# 5_-Display.net
KiCad netlist of a schematic drawn in Altium Designer
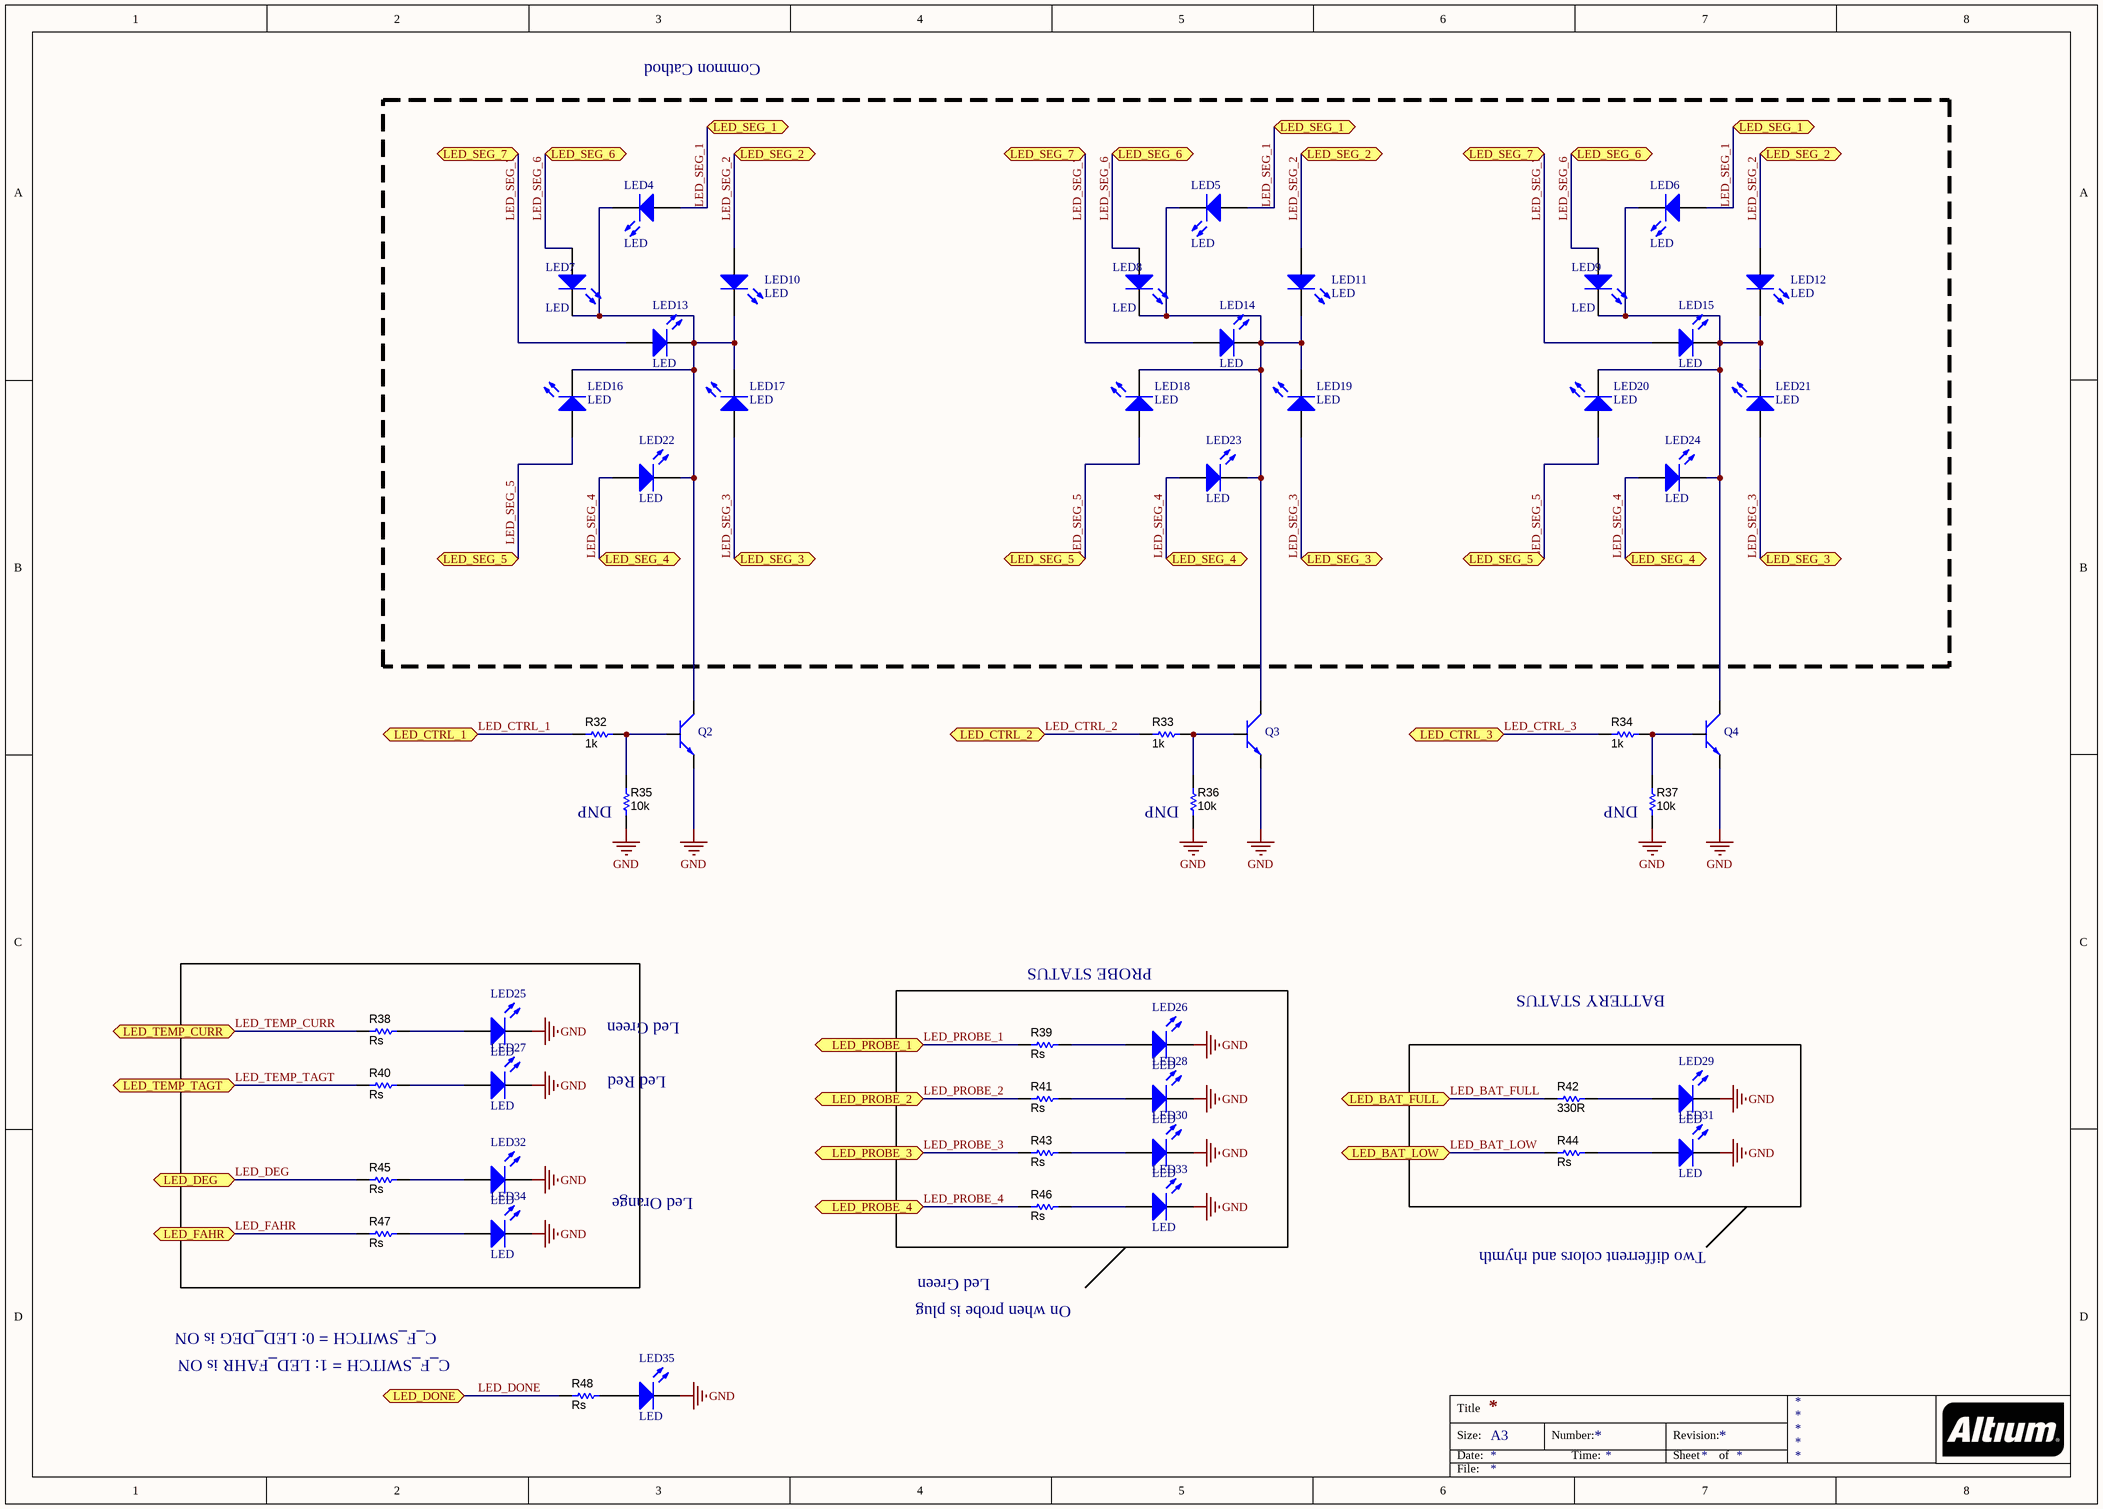
[diagram p0: [5]-Display.SchDoc]

(export (version "E")
  (design (tool "Eeschema 10.0.6"))
  (components
    (comp (ref "LED4")
      (value "LED")
      (footprint "LED-0603-YELLOW")
      (description "Typical INFRARED GaAs LED")
      (fields (field (name "PUBLISHER") "Altium Limited"))
      (libsource (lib "VTEKLib") (part "LED"))
    )
    (comp (ref "LED5")
      (value "LED")
      (footprint "LED-0603-YELLOW")
      (description "Typical INFRARED GaAs LED")
      (fields (field (name "PUBLISHER") "Altium Limited"))
      (libsource (lib "VTEKLib") (part "LED"))
    )
    (comp (ref "LED6")
      (value "LED")
      (footprint "LED-0603-YELLOW")
      (description "Typical INFRARED GaAs LED")
      (fields (field (name "PUBLISHER") "Altium Limited"))
      (libsource (lib "VTEKLib") (part "LED"))
    )
    (comp (ref "LED7")
      (value "LED")
      (footprint "LED-0603-YELLOW")
      (description "Typical INFRARED GaAs LED")
      (fields (field (name "PUBLISHER") "Altium Limited"))
      (libsource (lib "VTEKLib") (part "LED"))
    )
    (comp (ref "LED8")
      (value "LED")
      (footprint "LED-0603-YELLOW")
      (description "Typical INFRARED GaAs LED")
      (fields (field (name "PUBLISHER") "Altium Limited"))
      (libsource (lib "VTEKLib") (part "LED"))
    )
    (comp (ref "LED9")
      (value "LED")
      (footprint "LED-0603-YELLOW")
      (description "Typical INFRARED GaAs LED")
      (fields (field (name "PUBLISHER") "Altium Limited"))
      (libsource (lib "VTEKLib") (part "LED"))
    )
    (comp (ref "LED10")
      (value "LED")
      (footprint "LED-0603-YELLOW")
      (description "Typical INFRARED GaAs LED")
      (fields (field (name "PUBLISHER") "Altium Limited"))
      (libsource (lib "VTEKLib") (part "LED"))
    )
    (comp (ref "LED11")
      (value "LED")
      (footprint "LED-0603-YELLOW")
      (description "Typical INFRARED GaAs LED")
      (fields (field (name "PUBLISHER") "Altium Limited"))
      (libsource (lib "VTEKLib") (part "LED"))
    )
    (comp (ref "LED12")
      (value "LED")
      (footprint "LED-0603-YELLOW")
      (description "Typical INFRARED GaAs LED")
      (fields (field (name "PUBLISHER") "Altium Limited"))
      (libsource (lib "VTEKLib") (part "LED"))
    )
    (comp (ref "LED13")
      (value "LED")
      (footprint "LED-0603-YELLOW")
      (description "Typical INFRARED GaAs LED")
      (fields (field (name "PUBLISHER") "Altium Limited"))
      (libsource (lib "VTEKLib") (part "LED"))
    )
    (comp (ref "LED14")
      (value "LED")
      (footprint "LED-0603-YELLOW")
      (description "Typical INFRARED GaAs LED")
      (fields (field (name "PUBLISHER") "Altium Limited"))
      (libsource (lib "VTEKLib") (part "LED"))
    )
    (comp (ref "LED15")
      (value "LED")
      (footprint "LED-0603-YELLOW")
      (description "Typical INFRARED GaAs LED")
      (fields (field (name "PUBLISHER") "Altium Limited"))
      (libsource (lib "VTEKLib") (part "LED"))
    )
    (comp (ref "LED16")
      (value "LED")
      (footprint "LED-0603-YELLOW")
      (description "Typical INFRARED GaAs LED")
      (fields (field (name "PUBLISHER") "Altium Limited"))
      (libsource (lib "VTEKLib") (part "LED"))
    )
    (comp (ref "LED17")
      (value "LED")
      (footprint "LED-0603-YELLOW")
      (description "Typical INFRARED GaAs LED")
      (fields (field (name "PUBLISHER") "Altium Limited"))
      (libsource (lib "VTEKLib") (part "LED"))
    )
    (comp (ref "LED18")
      (value "LED")
      (footprint "LED-0603-YELLOW")
      (description "Typical INFRARED GaAs LED")
      (fields (field (name "PUBLISHER") "Altium Limited"))
      (libsource (lib "VTEKLib") (part "LED"))
    )
    (comp (ref "LED19")
      (value "LED")
      (footprint "LED-0603-YELLOW")
      (description "Typical INFRARED GaAs LED")
      (fields (field (name "PUBLISHER") "Altium Limited"))
      (libsource (lib "VTEKLib") (part "LED"))
    )
    (comp (ref "LED20")
      (value "LED")
      (footprint "LED-0603-YELLOW")
      (description "Typical INFRARED GaAs LED")
      (fields (field (name "PUBLISHER") "Altium Limited"))
      (libsource (lib "VTEKLib") (part "LED"))
    )
    (comp (ref "LED21")
      (value "LED")
      (footprint "LED-0603-YELLOW")
      (description "Typical INFRARED GaAs LED")
      (fields (field (name "PUBLISHER") "Altium Limited"))
      (libsource (lib "VTEKLib") (part "LED"))
    )
    (comp (ref "LED22")
      (value "LED")
      (footprint "LED-0603-YELLOW")
      (description "Typical INFRARED GaAs LED")
      (fields (field (name "PUBLISHER") "Altium Limited"))
      (libsource (lib "VTEKLib") (part "LED"))
    )
    (comp (ref "LED23")
      (value "LED")
      (footprint "LED-0603-YELLOW")
      (description "Typical INFRARED GaAs LED")
      (fields (field (name "PUBLISHER") "Altium Limited"))
      (libsource (lib "VTEKLib") (part "LED"))
    )
    (comp (ref "LED24")
      (value "LED")
      (footprint "LED-0603-YELLOW")
      (description "Typical INFRARED GaAs LED")
      (fields (field (name "PUBLISHER") "Altium Limited"))
      (libsource (lib "VTEKLib") (part "LED"))
    )
    (comp (ref "LED25")
      (value "LED")
      (footprint "LED-0603-YELLOW")
      (description "Typical INFRARED GaAs LED")
      (fields (field (name "PUBLISHER") "Altium Limited"))
      (libsource (lib "VTEKLib") (part "LED"))
    )
    (comp (ref "LED26")
      (value "LED")
      (footprint "LED-0603-YELLOW")
      (description "Typical INFRARED GaAs LED")
      (fields (field (name "PUBLISHER") "Altium Limited"))
      (libsource (lib "VTEKLib") (part "LED"))
    )
    (comp (ref "LED27")
      (value "LED")
      (footprint "LED-0603-YELLOW")
      (description "Typical INFRARED GaAs LED")
      (fields (field (name "PUBLISHER") "Altium Limited"))
      (libsource (lib "VTEKLib") (part "LED"))
    )
    (comp (ref "LED28")
      (value "LED")
      (footprint "LED-0603-YELLOW")
      (description "Typical INFRARED GaAs LED")
      (fields (field (name "PUBLISHER") "Altium Limited"))
      (libsource (lib "VTEKLib") (part "LED"))
    )
    (comp (ref "LED29")
      (value "LED")
      (footprint "LED-0603-YELLOW")
      (description "Typical INFRARED GaAs LED")
      (fields (field (name "PUBLISHER") "Altium Limited"))
      (libsource (lib "VTEKLib") (part "LED"))
    )
    (comp (ref "LED30")
      (value "LED")
      (footprint "LED-0603-YELLOW")
      (description "Typical INFRARED GaAs LED")
      (fields (field (name "PUBLISHER") "Altium Limited"))
      (libsource (lib "VTEKLib") (part "LED"))
    )
    (comp (ref "LED31")
      (value "LED")
      (footprint "LED-0603-YELLOW")
      (description "Typical INFRARED GaAs LED")
      (fields (field (name "PUBLISHER") "Altium Limited"))
      (libsource (lib "VTEKLib") (part "LED"))
    )
    (comp (ref "LED32")
      (value "LED")
      (footprint "LED-0603-YELLOW")
      (description "Typical INFRARED GaAs LED")
      (fields (field (name "PUBLISHER") "Altium Limited"))
      (libsource (lib "VTEKLib") (part "LED"))
    )
    (comp (ref "LED33")
      (value "LED")
      (footprint "LED-0603-YELLOW")
      (description "Typical INFRARED GaAs LED")
      (fields (field (name "PUBLISHER") "Altium Limited"))
      (libsource (lib "VTEKLib") (part "LED"))
    )
    (comp (ref "LED34")
      (value "LED")
      (footprint "LED-0603-YELLOW")
      (description "Typical INFRARED GaAs LED")
      (fields (field (name "PUBLISHER") "Altium Limited"))
      (libsource (lib "VTEKLib") (part "LED"))
    )
    (comp (ref "LED35")
      (value "LED")
      (footprint "LED-0603-YELLOW")
      (description "Typical INFRARED GaAs LED")
      (fields (field (name "PUBLISHER") "Altium Limited"))
      (libsource (lib "VTEKLib") (part "LED"))
    )
    (comp (ref "Q2")
      (value "MMBT2222A")
      (footprint "SOT23A")
      (description "NPN switching transistor  40V 600mA SOT23")
      (fields (field (name "MANUFACTURER") "Fairchild"))
      (libsource (lib "Cty1") (part "MMBT2222A"))
    )
    (comp (ref "Q3")
      (value "MMBT2222A")
      (footprint "SOT23A")
      (description "NPN switching transistor  40V 600mA SOT23")
      (fields (field (name "MANUFACTURER") "Fairchild"))
      (libsource (lib "Cty1") (part "MMBT2222A"))
    )
    (comp (ref "Q4")
      (value "MMBT2222A")
      (footprint "SOT23A")
      (description "NPN switching transistor  40V 600mA SOT23")
      (fields (field (name "MANUFACTURER") "Fairchild"))
      (libsource (lib "Cty1") (part "MMBT2222A"))
    )
    (comp (ref "R32")
      (value "1k")
      (footprint "0603")
      (description "RES, 1.00k ohm, 1%, 0.1W, 0603")
      (fields
        (field (name "PARTNUMBER") "CRCW06031K00FKEA")
        (field (name "MANUFACTURER") "Vishay-Dale")
        (field (name "PUBLISHER") "Texas Instruments")
      )
      (libsource (lib "tuongpv2") (part "R0603"))
    )
    (comp (ref "R33")
      (value "1k")
      (footprint "0603")
      (description "RES, 1.00k ohm, 1%, 0.1W, 0603")
      (fields
        (field (name "PARTNUMBER") "CRCW06031K00FKEA")
        (field (name "MANUFACTURER") "Vishay-Dale")
        (field (name "PUBLISHER") "Texas Instruments")
      )
      (libsource (lib "tuongpv2") (part "R0603"))
    )
    (comp (ref "R34")
      (value "1k")
      (footprint "0603")
      (description "RES, 1.00k ohm, 1%, 0.1W, 0603")
      (fields
        (field (name "PARTNUMBER") "CRCW06031K00FKEA")
        (field (name "MANUFACTURER") "Vishay-Dale")
        (field (name "PUBLISHER") "Texas Instruments")
      )
      (libsource (lib "tuongpv2") (part "R0603"))
    )
    (comp (ref "R35")
      (value "10k")
      (footprint "0603")
      (description "RES, 1.00k ohm, 1%, 0.1W, 0603")
      (fields
        (field (name "PARTNUMBER") "CRCW06031K00FKEA")
        (field (name "MANUFACTURER") "Vishay-Dale")
        (field (name "PUBLISHER") "Texas Instruments")
      )
      (libsource (lib "tuongpv2") (part "R0603"))
    )
    (comp (ref "R36")
      (value "10k")
      (footprint "0603")
      (description "RES, 1.00k ohm, 1%, 0.1W, 0603")
      (fields
        (field (name "PARTNUMBER") "CRCW06031K00FKEA")
        (field (name "MANUFACTURER") "Vishay-Dale")
        (field (name "PUBLISHER") "Texas Instruments")
      )
      (libsource (lib "tuongpv2") (part "R0603"))
    )
    (comp (ref "R37")
      (value "10k")
      (footprint "0603")
      (description "RES, 1.00k ohm, 1%, 0.1W, 0603")
      (fields
        (field (name "PARTNUMBER") "CRCW06031K00FKEA")
        (field (name "MANUFACTURER") "Vishay-Dale")
        (field (name "PUBLISHER") "Texas Instruments")
      )
      (libsource (lib "tuongpv2") (part "R0603"))
    )
    (comp (ref "R38")
      (value "Rs")
      (footprint "0603")
      (description "RES, 1.00k ohm, 1%, 0.1W, 0603")
      (fields
        (field (name "PARTNUMBER") "CRCW06031K00FKEA")
        (field (name "MANUFACTURER") "Vishay-Dale")
        (field (name "PUBLISHER") "Texas Instruments")
      )
      (libsource (lib "tuongpv2") (part "R0603"))
    )
    (comp (ref "R39")
      (value "Rs")
      (footprint "0603")
      (description "RES, 1.00k ohm, 1%, 0.1W, 0603")
      (fields
        (field (name "PARTNUMBER") "CRCW06031K00FKEA")
        (field (name "MANUFACTURER") "Vishay-Dale")
        (field (name "PUBLISHER") "Texas Instruments")
      )
      (libsource (lib "tuongpv2") (part "R0603"))
    )
    (comp (ref "R40")
      (value "Rs")
      (footprint "0603")
      (description "RES, 1.00k ohm, 1%, 0.1W, 0603")
      (fields
        (field (name "PARTNUMBER") "CRCW06031K00FKEA")
        (field (name "MANUFACTURER") "Vishay-Dale")
        (field (name "PUBLISHER") "Texas Instruments")
      )
      (libsource (lib "tuongpv2") (part "R0603"))
    )
    (comp (ref "R41")
      (value "Rs")
      (footprint "0603")
      (description "RES, 1.00k ohm, 1%, 0.1W, 0603")
      (fields
        (field (name "PARTNUMBER") "CRCW06031K00FKEA")
        (field (name "MANUFACTURER") "Vishay-Dale")
        (field (name "PUBLISHER") "Texas Instruments")
      )
      (libsource (lib "tuongpv2") (part "R0603"))
    )
    (comp (ref "R42")
      (value "330R")
      (footprint "0603")
      (description "RES, 1.00k ohm, 1%, 0.1W, 0603")
      (fields
        (field (name "PARTNUMBER") "CRCW06031K00FKEA")
        (field (name "MANUFACTURER") "Vishay-Dale")
        (field (name "PUBLISHER") "Texas Instruments")
      )
      (libsource (lib "tuongpv2") (part "R0603"))
    )
    (comp (ref "R43")
      (value "Rs")
      (footprint "0603")
      (description "RES, 1.00k ohm, 1%, 0.1W, 0603")
      (fields
        (field (name "PARTNUMBER") "CRCW06031K00FKEA")
        (field (name "MANUFACTURER") "Vishay-Dale")
        (field (name "PUBLISHER") "Texas Instruments")
      )
      (libsource (lib "tuongpv2") (part "R0603"))
    )
    (comp (ref "R44")
      (value "Rs")
      (footprint "0603")
      (description "RES, 1.00k ohm, 1%, 0.1W, 0603")
      (fields
        (field (name "PARTNUMBER") "CRCW06031K00FKEA")
        (field (name "MANUFACTURER") "Vishay-Dale")
        (field (name "PUBLISHER") "Texas Instruments")
      )
      (libsource (lib "tuongpv2") (part "R0603"))
    )
    (comp (ref "R45")
      (value "Rs")
      (footprint "0603")
      (description "RES, 1.00k ohm, 1%, 0.1W, 0603")
      (fields
        (field (name "PARTNUMBER") "CRCW06031K00FKEA")
        (field (name "MANUFACTURER") "Vishay-Dale")
        (field (name "PUBLISHER") "Texas Instruments")
      )
      (libsource (lib "tuongpv2") (part "R0603"))
    )
    (comp (ref "R46")
      (value "Rs")
      (footprint "0603")
      (description "RES, 1.00k ohm, 1%, 0.1W, 0603")
      (fields
        (field (name "PARTNUMBER") "CRCW06031K00FKEA")
        (field (name "MANUFACTURER") "Vishay-Dale")
        (field (name "PUBLISHER") "Texas Instruments")
      )
      (libsource (lib "tuongpv2") (part "R0603"))
    )
    (comp (ref "R47")
      (value "Rs")
      (footprint "0603")
      (description "RES, 1.00k ohm, 1%, 0.1W, 0603")
      (fields
        (field (name "PARTNUMBER") "CRCW06031K00FKEA")
        (field (name "MANUFACTURER") "Vishay-Dale")
        (field (name "PUBLISHER") "Texas Instruments")
      )
      (libsource (lib "tuongpv2") (part "R0603"))
    )
    (comp (ref "R48")
      (value "Rs")
      (footprint "0603")
      (description "RES, 1.00k ohm, 1%, 0.1W, 0603")
      (fields
        (field (name "PARTNUMBER") "CRCW06031K00FKEA")
        (field (name "MANUFACTURER") "Vishay-Dale")
        (field (name "PUBLISHER") "Texas Instruments")
      )
      (libsource (lib "tuongpv2") (part "R0603"))
    )
  )
  (nets
    (net (code "1") (name "/LED_BAT_FULL") (class "Default")
      (node (ref "R42") (pin "2") (pinfunction "2_2") (pintype "passive"))
    )
    (net (code "2") (name "/LED_BAT_LOW") (class "Default")
      (node (ref "R44") (pin "2") (pinfunction "2_2") (pintype "passive"))
    )
    (net (code "3") (name "/LED_CTRL_1") (class "Default")
      (node (ref "R32") (pin "1") (pinfunction "1_1") (pintype "passive"))
    )
    (net (code "4") (name "/LED_CTRL_2") (class "Default")
      (node (ref "R33") (pin "1") (pinfunction "1_1") (pintype "passive"))
    )
    (net (code "5") (name "/LED_CTRL_3") (class "Default")
      (node (ref "R34") (pin "1") (pinfunction "1_1") (pintype "passive"))
    )
    (net (code "6") (name "/LED_DEG") (class "Default")
      (node (ref "R45") (pin "2") (pinfunction "2_2") (pintype "passive"))
    )
    (net (code "7") (name "/LED_DONE") (class "Default")
      (node (ref "R48") (pin "2") (pinfunction "2_2") (pintype "passive"))
    )
    (net (code "8") (name "/LED_FAHR") (class "Default")
      (node (ref "R47") (pin "2") (pinfunction "2_2") (pintype "passive"))
    )
    (net (code "9") (name "/LED_PROBE_1") (class "Default")
      (node (ref "R39") (pin "2") (pinfunction "2_2") (pintype "passive"))
    )
    (net (code "10") (name "/LED_PROBE_2") (class "Default")
      (node (ref "R41") (pin "2") (pinfunction "2_2") (pintype "passive"))
    )
    (net (code "11") (name "/LED_PROBE_3") (class "Default")
      (node (ref "R43") (pin "2") (pinfunction "2_2") (pintype "passive"))
    )
    (net (code "12") (name "/LED_PROBE_4") (class "Default")
      (node (ref "R46") (pin "2") (pinfunction "2_2") (pintype "passive"))
    )
    (net (code "13") (name "/LED_SEG_1") (class "Default")
      (node (ref "LED4") (pin "1") (pinfunction "A_1") (pintype "passive"))
      (node (ref "LED5") (pin "1") (pinfunction "A_1") (pintype "passive"))
      (node (ref "LED6") (pin "1") (pinfunction "A_1") (pintype "passive"))
    )
    (net (code "14") (name "/LED_SEG_2") (class "Default")
      (node (ref "LED10") (pin "1") (pinfunction "A_1") (pintype "passive"))
      (node (ref "LED11") (pin "1") (pinfunction "A_1") (pintype "passive"))
      (node (ref "LED12") (pin "1") (pinfunction "A_1") (pintype "passive"))
    )
    (net (code "15") (name "/LED_SEG_3") (class "Default")
      (node (ref "LED17") (pin "1") (pinfunction "A_1") (pintype "passive"))
      (node (ref "LED19") (pin "1") (pinfunction "A_1") (pintype "passive"))
      (node (ref "LED21") (pin "1") (pinfunction "A_1") (pintype "passive"))
    )
    (net (code "16") (name "/LED_SEG_4") (class "Default")
      (node (ref "LED22") (pin "1") (pinfunction "A_1") (pintype "passive"))
      (node (ref "LED23") (pin "1") (pinfunction "A_1") (pintype "passive"))
      (node (ref "LED24") (pin "1") (pinfunction "A_1") (pintype "passive"))
    )
    (net (code "17") (name "/LED_SEG_5") (class "Default")
      (node (ref "LED16") (pin "1") (pinfunction "A_1") (pintype "passive"))
      (node (ref "LED18") (pin "1") (pinfunction "A_1") (pintype "passive"))
      (node (ref "LED20") (pin "1") (pinfunction "A_1") (pintype "passive"))
    )
    (net (code "18") (name "/LED_SEG_6") (class "Default")
      (node (ref "LED7") (pin "1") (pinfunction "A_1") (pintype "passive"))
      (node (ref "LED8") (pin "1") (pinfunction "A_1") (pintype "passive"))
      (node (ref "LED9") (pin "1") (pinfunction "A_1") (pintype "passive"))
    )
    (net (code "19") (name "/LED_SEG_7") (class "Default")
      (node (ref "LED13") (pin "1") (pinfunction "A_1") (pintype "passive"))
      (node (ref "LED14") (pin "1") (pinfunction "A_1") (pintype "passive"))
      (node (ref "LED15") (pin "1") (pinfunction "A_1") (pintype "passive"))
    )
    (net (code "20") (name "/LED_TEMP_CURR") (class "Default")
      (node (ref "R38") (pin "2") (pinfunction "2_2") (pintype "passive"))
    )
    (net (code "21") (name "/LED_TEMP_TAGT") (class "Default")
      (node (ref "R40") (pin "2") (pinfunction "2_2") (pintype "passive"))
    )
    (net (code "22") (name "GND") (class "Default")
      (node (ref "LED25") (pin "2") (pinfunction "K_2") (pintype "passive"))
      (node (ref "LED26") (pin "2") (pinfunction "K_2") (pintype "passive"))
      (node (ref "LED27") (pin "2") (pinfunction "K_2") (pintype "passive"))
      (node (ref "LED28") (pin "2") (pinfunction "K_2") (pintype "passive"))
      (node (ref "LED29") (pin "2") (pinfunction "K_2") (pintype "passive"))
      (node (ref "LED30") (pin "2") (pinfunction "K_2") (pintype "passive"))
      (node (ref "LED31") (pin "2") (pinfunction "K_2") (pintype "passive"))
      (node (ref "LED32") (pin "2") (pinfunction "K_2") (pintype "passive"))
      (node (ref "LED33") (pin "2") (pinfunction "K_2") (pintype "passive"))
      (node (ref "LED34") (pin "2") (pinfunction "K_2") (pintype "passive"))
      (node (ref "LED35") (pin "2") (pinfunction "K_2") (pintype "passive"))
      (node (ref "Q2") (pin "2") (pinfunction "E_2") (pintype "passive"))
      (node (ref "Q3") (pin "2") (pinfunction "E_2") (pintype "passive"))
      (node (ref "Q4") (pin "2") (pinfunction "E_2") (pintype "passive"))
      (node (ref "R35") (pin "1") (pinfunction "1_1") (pintype "passive"))
      (node (ref "R36") (pin "1") (pinfunction "1_1") (pintype "passive"))
      (node (ref "R37") (pin "1") (pinfunction "1_1") (pintype "passive"))
    )
    (net (code "23") (name "Net-(LED10-K)") (class "Default")
      (node (ref "LED10") (pin "2") (pinfunction "K_2") (pintype "passive"))
      (node (ref "LED13") (pin "2") (pinfunction "K_2") (pintype "passive"))
      (node (ref "LED16") (pin "2") (pinfunction "K_2") (pintype "passive"))
      (node (ref "LED17") (pin "2") (pinfunction "K_2") (pintype "passive"))
      (node (ref "LED22") (pin "2") (pinfunction "K_2") (pintype "passive"))
      (node (ref "LED4") (pin "2") (pinfunction "K_2") (pintype "passive"))
      (node (ref "LED7") (pin "2") (pinfunction "K_2") (pintype "passive"))
      (node (ref "Q2") (pin "3") (pinfunction "C_3") (pintype "passive"))
    )
    (net (code "24") (name "Net-(LED11-K)") (class "Default")
      (node (ref "LED11") (pin "2") (pinfunction "K_2") (pintype "passive"))
      (node (ref "LED14") (pin "2") (pinfunction "K_2") (pintype "passive"))
      (node (ref "LED18") (pin "2") (pinfunction "K_2") (pintype "passive"))
      (node (ref "LED19") (pin "2") (pinfunction "K_2") (pintype "passive"))
      (node (ref "LED23") (pin "2") (pinfunction "K_2") (pintype "passive"))
      (node (ref "LED5") (pin "2") (pinfunction "K_2") (pintype "passive"))
      (node (ref "LED8") (pin "2") (pinfunction "K_2") (pintype "passive"))
      (node (ref "Q3") (pin "3") (pinfunction "C_3") (pintype "passive"))
    )
    (net (code "25") (name "Net-(LED12-K)") (class "Default")
      (node (ref "LED12") (pin "2") (pinfunction "K_2") (pintype "passive"))
      (node (ref "LED15") (pin "2") (pinfunction "K_2") (pintype "passive"))
      (node (ref "LED20") (pin "2") (pinfunction "K_2") (pintype "passive"))
      (node (ref "LED21") (pin "2") (pinfunction "K_2") (pintype "passive"))
      (node (ref "LED24") (pin "2") (pinfunction "K_2") (pintype "passive"))
      (node (ref "LED6") (pin "2") (pinfunction "K_2") (pintype "passive"))
      (node (ref "LED9") (pin "2") (pinfunction "K_2") (pintype "passive"))
      (node (ref "Q4") (pin "3") (pinfunction "C_3") (pintype "passive"))
    )
    (net (code "26") (name "Net-(LED25-A)") (class "Default")
      (node (ref "LED25") (pin "1") (pinfunction "A_1") (pintype "passive"))
      (node (ref "R38") (pin "1") (pinfunction "1_1") (pintype "passive"))
    )
    (net (code "27") (name "Net-(LED26-A)") (class "Default")
      (node (ref "LED26") (pin "1") (pinfunction "A_1") (pintype "passive"))
      (node (ref "R39") (pin "1") (pinfunction "1_1") (pintype "passive"))
    )
    (net (code "28") (name "Net-(LED27-A)") (class "Default")
      (node (ref "LED27") (pin "1") (pinfunction "A_1") (pintype "passive"))
      (node (ref "R40") (pin "1") (pinfunction "1_1") (pintype "passive"))
    )
    (net (code "29") (name "Net-(LED28-A)") (class "Default")
      (node (ref "LED28") (pin "1") (pinfunction "A_1") (pintype "passive"))
      (node (ref "R41") (pin "1") (pinfunction "1_1") (pintype "passive"))
    )
    (net (code "30") (name "Net-(LED29-A)") (class "Default")
      (node (ref "LED29") (pin "1") (pinfunction "A_1") (pintype "passive"))
      (node (ref "R42") (pin "1") (pinfunction "1_1") (pintype "passive"))
    )
    (net (code "31") (name "Net-(LED30-A)") (class "Default")
      (node (ref "LED30") (pin "1") (pinfunction "A_1") (pintype "passive"))
      (node (ref "R43") (pin "1") (pinfunction "1_1") (pintype "passive"))
    )
    (net (code "32") (name "Net-(LED31-A)") (class "Default")
      (node (ref "LED31") (pin "1") (pinfunction "A_1") (pintype "passive"))
      (node (ref "R44") (pin "1") (pinfunction "1_1") (pintype "passive"))
    )
    (net (code "33") (name "Net-(LED32-A)") (class "Default")
      (node (ref "LED32") (pin "1") (pinfunction "A_1") (pintype "passive"))
      (node (ref "R45") (pin "1") (pinfunction "1_1") (pintype "passive"))
    )
    (net (code "34") (name "Net-(LED33-A)") (class "Default")
      (node (ref "LED33") (pin "1") (pinfunction "A_1") (pintype "passive"))
      (node (ref "R46") (pin "1") (pinfunction "1_1") (pintype "passive"))
    )
    (net (code "35") (name "Net-(LED34-A)") (class "Default")
      (node (ref "LED34") (pin "1") (pinfunction "A_1") (pintype "passive"))
      (node (ref "R47") (pin "1") (pinfunction "1_1") (pintype "passive"))
    )
    (net (code "36") (name "Net-(LED35-A)") (class "Default")
      (node (ref "LED35") (pin "1") (pinfunction "A_1") (pintype "passive"))
      (node (ref "R48") (pin "1") (pinfunction "1_1") (pintype "passive"))
    )
    (net (code "37") (name "Net-(Q2-B)") (class "Default")
      (node (ref "Q2") (pin "1") (pinfunction "B_1") (pintype "passive"))
      (node (ref "R32") (pin "2") (pinfunction "2_2") (pintype "passive"))
      (node (ref "R35") (pin "2") (pinfunction "2_2") (pintype "passive"))
    )
    (net (code "38") (name "Net-(Q3-B)") (class "Default")
      (node (ref "Q3") (pin "1") (pinfunction "B_1") (pintype "passive"))
      (node (ref "R33") (pin "2") (pinfunction "2_2") (pintype "passive"))
      (node (ref "R36") (pin "2") (pinfunction "2_2") (pintype "passive"))
    )
    (net (code "39") (name "Net-(Q4-B)") (class "Default")
      (node (ref "Q4") (pin "1") (pinfunction "B_1") (pintype "passive"))
      (node (ref "R34") (pin "2") (pinfunction "2_2") (pintype "passive"))
      (node (ref "R37") (pin "2") (pinfunction "2_2") (pintype "passive"))
    )
  )
)
